# aparture_v1_controller.net
KiCad netlist of a schematic drawn in EAGLE
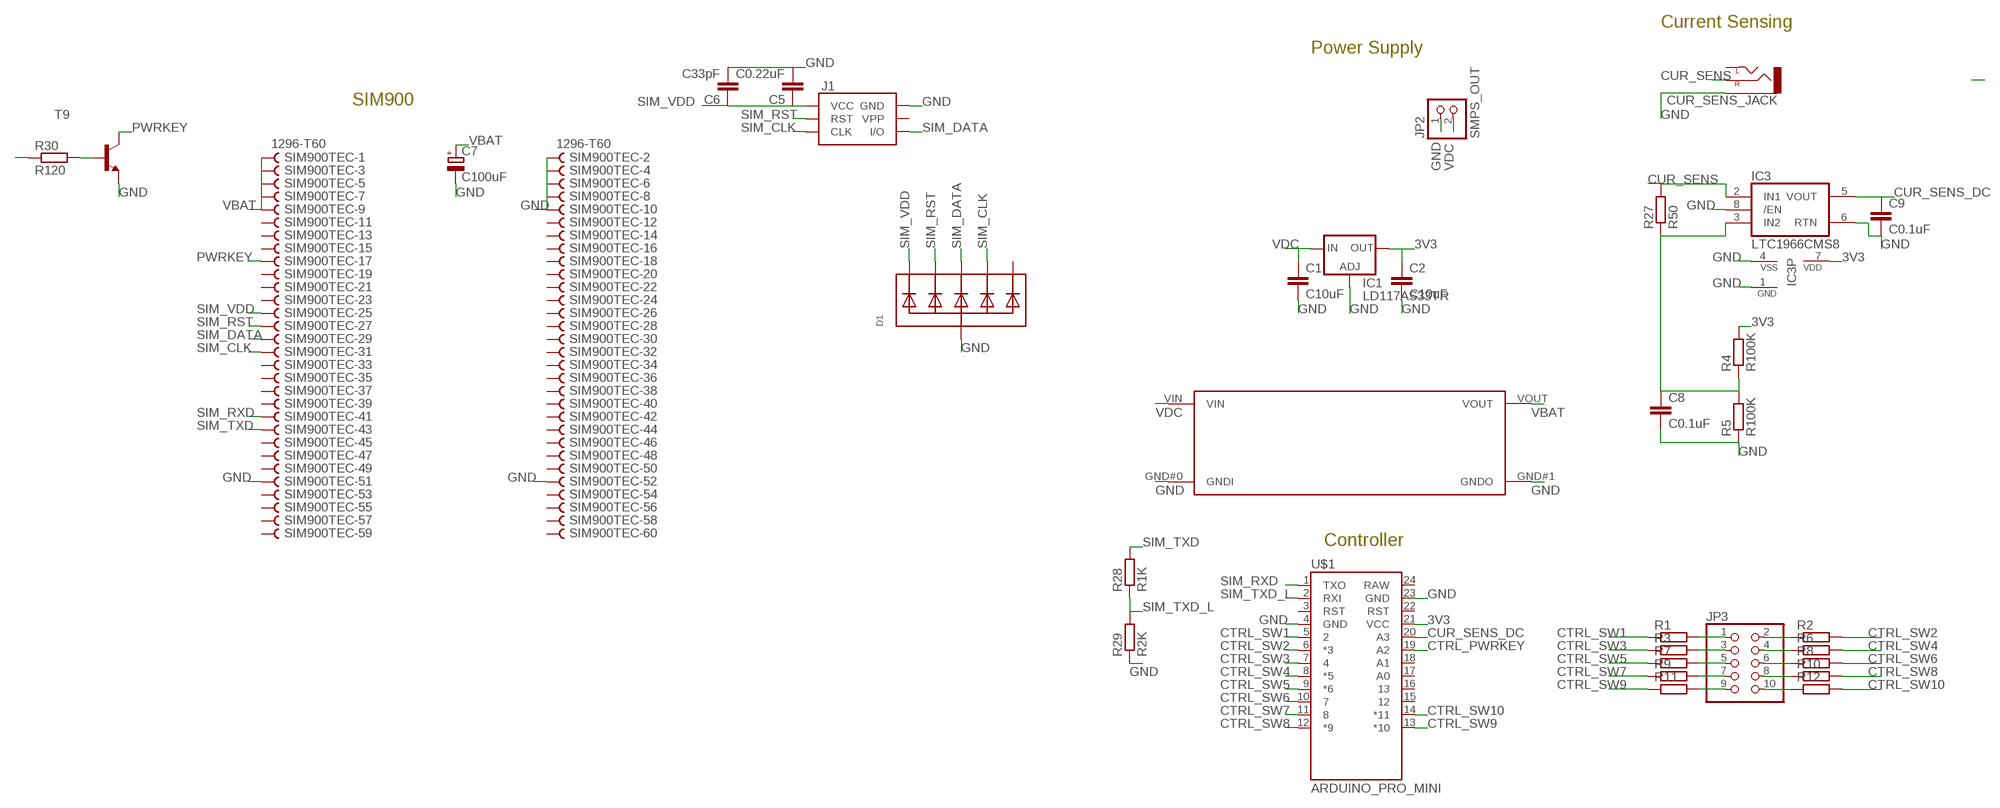
[diagram p0: schematic, sheet 1]

(export (version "E")
  (design (tool "Eeschema 10.0.6"))
  (components
    (comp (ref "C1")
      (value "C10uF")
      (footprint "eagle-import:C0805")
      (libsource (lib "eagle-import") (part "C-EUC0805"))
    )
    (comp (ref "C2")
      (value "C10uF")
      (footprint "eagle-import:C0805")
      (libsource (lib "eagle-import") (part "C-EUC0805"))
    )
    (comp (ref "C5")
      (value "C0.22uF")
      (footprint "eagle-import:C0805")
      (libsource (lib "eagle-import") (part "C-EUC0805"))
    )
    (comp (ref "C6")
      (value "C33pF")
      (footprint "eagle-import:C0805")
      (libsource (lib "eagle-import") (part "C-EUC0805"))
    )
    (comp (ref "C7")
      (value "C100uF")
      (footprint "eagle-import:153CLV-0605")
      (libsource (lib "eagle-import") (part "CPOL-EU153CLV-0605"))
    )
    (comp (ref "C8")
      (value "C0.1uF")
      (footprint "eagle-import:C0805")
      (libsource (lib "eagle-import") (part "C-EUC0805"))
    )
    (comp (ref "C9")
      (value "C0.1uF")
      (footprint "eagle-import:C0805")
      (libsource (lib "eagle-import") (part "C-EUC0805"))
    )
    (comp (ref "CUR_SENS_JACK")
      (value "AUDIO-JACKSMD2")
      (footprint "eagle-import:AUDIO-JACK-3.5MM-SMD")
      (libsource (lib "eagle-import") (part "AUDIO-JACKSMD2"))
    )
    (comp (ref "D1")
      (value "TVSARRAY_5LANE")
      (footprint "eagle-import:SOT363")
      (libsource (lib "eagle-import") (part "TVSARRAY_5LANE"))
    )
    (comp (ref "IC1")
      (value "LD117AS33TR")
      (footprint "eagle-import:SOT223")
      (libsource (lib "eagle-import") (part "LD117A?S33TR"))
    )
    (comp (ref "IC3")
      (value "LTC1966CMS8")
      (footprint "eagle-import:MSOP8")
      (libsource (lib "eagle-import") (part "LTC1966MS8C"))
    )
    (comp (ref "J1")
      (value "SIMHOLDERSIM")
      (footprint "eagle-import:SIMHOLDER")
      (libsource (lib "eagle-import") (part "SIMHOLDERSIM"))
    )
    (comp (ref "JP2")
      (value "SMPS_OUT")
      (footprint "eagle-import:1X02")
      (libsource (lib "eagle-import") (part "PINHD-1X2"))
    )
    (comp (ref "JP3")
      (value "PINHD-2X5")
      (footprint "eagle-import:2X05")
      (libsource (lib "eagle-import") (part "PINHD-2X5"))
    )
    (comp (ref "R1")
      (value "R-EU_R0603")
      (footprint "eagle-import:R0603")
      (libsource (lib "eagle-import") (part "R-EU_R0603"))
    )
    (comp (ref "R2")
      (value "R-EU_R0603")
      (footprint "eagle-import:R0603")
      (libsource (lib "eagle-import") (part "R-EU_R0603"))
    )
    (comp (ref "R3")
      (value "R-EU_R0603")
      (footprint "eagle-import:R0603")
      (libsource (lib "eagle-import") (part "R-EU_R0603"))
    )
    (comp (ref "R4")
      (value "R100K")
      (footprint "eagle-import:M0805")
      (libsource (lib "eagle-import") (part "resistor_R-EU_M0805"))
    )
    (comp (ref "R5")
      (value "R100K")
      (footprint "eagle-import:M0805")
      (libsource (lib "eagle-import") (part "resistor_R-EU_M0805"))
    )
    (comp (ref "R6")
      (value "R-EU_R0603")
      (footprint "eagle-import:R0603")
      (libsource (lib "eagle-import") (part "R-EU_R0603"))
    )
    (comp (ref "R7")
      (value "R-EU_R0603")
      (footprint "eagle-import:R0603")
      (libsource (lib "eagle-import") (part "R-EU_R0603"))
    )
    (comp (ref "R8")
      (value "R-EU_R0603")
      (footprint "eagle-import:R0603")
      (libsource (lib "eagle-import") (part "R-EU_R0603"))
    )
    (comp (ref "R9")
      (value "R-EU_R0603")
      (footprint "eagle-import:R0603")
      (libsource (lib "eagle-import") (part "R-EU_R0603"))
    )
    (comp (ref "R10")
      (value "R-EU_R0603")
      (footprint "eagle-import:R0603")
      (libsource (lib "eagle-import") (part "R-EU_R0603"))
    )
    (comp (ref "R11")
      (value "R-EU_R0603")
      (footprint "eagle-import:R0603")
      (libsource (lib "eagle-import") (part "R-EU_R0603"))
    )
    (comp (ref "R12")
      (value "R-EU_R0603")
      (footprint "eagle-import:R0603")
      (libsource (lib "eagle-import") (part "R-EU_R0603"))
    )
    (comp (ref "R27")
      (value "R50")
      (footprint "eagle-import:M0805")
      (libsource (lib "eagle-import") (part "resistor_R-EU_M0805"))
    )
    (comp (ref "R28")
      (value "R1K")
      (footprint "eagle-import:M0805")
      (libsource (lib "eagle-import") (part "resistor_R-EU_M0805"))
    )
    (comp (ref "R29")
      (value "R2K")
      (footprint "eagle-import:M0805")
      (libsource (lib "eagle-import") (part "resistor_R-EU_M0805"))
    )
    (comp (ref "R30")
      (value "R120")
      (footprint "eagle-import:M0805")
      (libsource (lib "eagle-import") (part "resistor_R-EU_M0805"))
    )
    (comp (ref "SIM900TEC")
      (value "1296-T60")
      (footprint "eagle-import:1296-60")
      (libsource (lib "eagle-import") (part "1296-T60"))
    )
    (comp (ref "T9")
      (value "MMBT2222ALT1-NPN-SOT23-BEC")
      (footprint "eagle-import:SOT23-BEC")
      (libsource (lib "eagle-import") (part "-NPN-SOT23-BECMMBT2222ALT1"))
    )
    (comp (ref "U$1")
      (value "ARDUINO_PRO_MINI")
      (footprint "eagle-import:ARDUINO_PRO_MINI")
      (libsource (lib "eagle-import") (part "ARDUINO_PRO_MINI"))
    )
    (comp (ref "VOL_REG_SIM900")
      (value "DCDCMODULE")
      (footprint "eagle-import:DCDCMODULE")
      (libsource (lib "eagle-import") (part "DCDCMODULE"))
    )
  )
  (nets
    (net (code "1") (name "/3V3") (class "Default")
      (node (ref "C2") (pin "1") (pinfunction "1_1") (pintype "passive"))
      (node (ref "IC1") (pin "4") (pinfunction "OUT_4") (pintype "passive"))
      (node (ref "IC3") (pin "7") (pinfunction "VDD_7") (pintype "power_in"))
      (node (ref "R4") (pin "2") (pinfunction "2_2") (pintype "passive"))
      (node (ref "U$1") (pin "21") (pinfunction "VCC_21") (pintype "bidirectional"))
    )
    (net (code "2") (name "/CTRL_PWRKEY") (class "Default")
      (node (ref "R30") (pin "1") (pinfunction "1_1") (pintype "passive"))
      (node (ref "U$1") (pin "19") (pinfunction "A2_19") (pintype "bidirectional"))
    )
    (net (code "3") (name "/CTRL_SW1") (class "Default")
      (node (ref "R1") (pin "1") (pinfunction "1_1") (pintype "passive"))
      (node (ref "U$1") (pin "5") (pinfunction "2_5") (pintype "bidirectional"))
    )
    (net (code "4") (name "/CTRL_SW2") (class "Default")
      (node (ref "R2") (pin "2") (pinfunction "2_2") (pintype "passive"))
      (node (ref "U$1") (pin "6") (pinfunction "*3_6") (pintype "bidirectional"))
    )
    (net (code "5") (name "/CTRL_SW3") (class "Default")
      (node (ref "R3") (pin "1") (pinfunction "1_1") (pintype "passive"))
      (node (ref "U$1") (pin "7") (pinfunction "4_7") (pintype "bidirectional"))
    )
    (net (code "6") (name "/CTRL_SW4") (class "Default")
      (node (ref "R6") (pin "2") (pinfunction "2_2") (pintype "passive"))
      (node (ref "U$1") (pin "8") (pinfunction "*5_8") (pintype "bidirectional"))
    )
    (net (code "7") (name "/CTRL_SW5") (class "Default")
      (node (ref "R7") (pin "1") (pinfunction "1_1") (pintype "passive"))
      (node (ref "U$1") (pin "9") (pinfunction "*6_9") (pintype "bidirectional"))
    )
    (net (code "8") (name "/CTRL_SW6") (class "Default")
      (node (ref "R8") (pin "2") (pinfunction "2_2") (pintype "passive"))
      (node (ref "U$1") (pin "10") (pinfunction "7_10") (pintype "bidirectional"))
    )
    (net (code "9") (name "/CTRL_SW7") (class "Default")
      (node (ref "R9") (pin "1") (pinfunction "1_1") (pintype "passive"))
      (node (ref "U$1") (pin "11") (pinfunction "8_11") (pintype "bidirectional"))
    )
    (net (code "10") (name "/CTRL_SW8") (class "Default")
      (node (ref "R10") (pin "2") (pinfunction "2_2") (pintype "passive"))
      (node (ref "U$1") (pin "12") (pinfunction "*9_12") (pintype "bidirectional"))
    )
    (net (code "11") (name "/CTRL_SW9") (class "Default")
      (node (ref "R11") (pin "1") (pinfunction "1_1") (pintype "passive"))
      (node (ref "U$1") (pin "13") (pinfunction "*10_13") (pintype "bidirectional"))
    )
    (net (code "12") (name "/CTRL_SW10") (class "Default")
      (node (ref "R12") (pin "2") (pinfunction "2_2") (pintype "passive"))
      (node (ref "U$1") (pin "14") (pinfunction "*11_14") (pintype "bidirectional"))
    )
    (net (code "13") (name "/CUR_SENS") (class "Default")
      (node (ref "CUR_SENS_JACK") (pin "RING") (pinfunction "RIGHT_RING") (pintype "bidirectional"))
      (node (ref "IC3") (pin "2") (pinfunction "IN1_2") (pintype "input"))
      (node (ref "R27") (pin "2") (pinfunction "2_2") (pintype "passive"))
    )
    (net (code "14") (name "/CUR_SENS_DC") (class "Default")
      (node (ref "C9") (pin "1") (pinfunction "1_1") (pintype "passive"))
      (node (ref "IC3") (pin "5") (pinfunction "VOUT_5") (pintype "output"))
      (node (ref "U$1") (pin "20") (pinfunction "A3_20") (pintype "bidirectional"))
    )
    (net (code "15") (name "/GND") (class "Default")
      (node (ref "C1") (pin "2") (pinfunction "2_2") (pintype "passive"))
      (node (ref "C2") (pin "2") (pinfunction "2_2") (pintype "passive"))
      (node (ref "C5") (pin "2") (pinfunction "2_2") (pintype "passive"))
      (node (ref "C6") (pin "2") (pinfunction "2_2") (pintype "passive"))
      (node (ref "C7") (pin "-") (pinfunction "-_-") (pintype "passive"))
      (node (ref "C8") (pin "2") (pinfunction "2_2") (pintype "passive"))
      (node (ref "C9") (pin "2") (pinfunction "2_2") (pintype "passive"))
      (node (ref "CUR_SENS_JACK") (pin "SLEEVE") (pinfunction "SLEEVE_SLEEVE") (pintype "bidirectional"))
      (node (ref "D1") (pin "2") (pinfunction "A_2") (pintype "passive"))
      (node (ref "IC1") (pin "1") (pinfunction "ADJ_1") (pintype "input"))
      (node (ref "IC3") (pin "1") (pinfunction "GND_1") (pintype "power_in"))
      (node (ref "IC3") (pin "4") (pinfunction "VSS_4") (pintype "power_in"))
      (node (ref "IC3") (pin "6") (pinfunction "RTN_6") (pintype "passive"))
      (node (ref "IC3") (pin "8") (pinfunction "/EN_8") (pintype "input"))
      (node (ref "J1") (pin "C5") (pinfunction "GND_C5") (pintype "power_in"))
      (node (ref "JP2") (pin "1") (pinfunction "1_1") (pintype "passive"))
      (node (ref "R29") (pin "1") (pinfunction "1_1") (pintype "passive"))
      (node (ref "R5") (pin "1") (pinfunction "1_1") (pintype "passive"))
      (node (ref "SIM900TEC") (pin "10") (pinfunction "B_10") (pintype "passive"))
      (node (ref "SIM900TEC") (pin "2") (pinfunction "B_2") (pintype "passive"))
      (node (ref "SIM900TEC") (pin "4") (pinfunction "B_4") (pintype "passive"))
      (node (ref "SIM900TEC") (pin "51") (pinfunction "B_51") (pintype "passive"))
      (node (ref "SIM900TEC") (pin "52") (pinfunction "B_52") (pintype "passive"))
      (node (ref "SIM900TEC") (pin "6") (pinfunction "B_6") (pintype "passive"))
      (node (ref "SIM900TEC") (pin "8") (pinfunction "B_8") (pintype "passive"))
      (node (ref "T9") (pin "E") (pinfunction "E_E") (pintype "passive"))
      (node (ref "U$1") (pin "23") (pinfunction "GND_23") (pintype "bidirectional"))
      (node (ref "U$1") (pin "4") (pinfunction "GND_4") (pintype "bidirectional"))
      (node (ref "VOL_REG_SIM900") (pin "GND#0") (pinfunction "GNDI_GND#0") (pintype "bidirectional"))
      (node (ref "VOL_REG_SIM900") (pin "GND#1") (pinfunction "GNDO_GND#1") (pintype "bidirectional"))
    )
    (net (code "16") (name "/PWRKEY") (class "Default")
      (node (ref "SIM900TEC") (pin "17") (pinfunction "B_17") (pintype "passive"))
      (node (ref "T9") (pin "C") (pinfunction "C_C") (pintype "passive"))
    )
    (net (code "17") (name "/SIM_CLK") (class "Default")
      (node (ref "D1") (pin "5") (pinfunction "C4_5") (pintype "passive"))
      (node (ref "J1") (pin "C3") (pinfunction "CLK_C3") (pintype "input"))
      (node (ref "SIM900TEC") (pin "31") (pinfunction "B_31") (pintype "passive"))
    )
    (net (code "18") (name "/SIM_DATA") (class "Default")
      (node (ref "D1") (pin "4") (pinfunction "C3_4") (pintype "passive"))
      (node (ref "J1") (pin "C7") (pinfunction "I/O_C7") (pintype "bidirectional"))
      (node (ref "SIM900TEC") (pin "29") (pinfunction "B_29") (pintype "passive"))
    )
    (net (code "19") (name "/SIM_RST") (class "Default")
      (node (ref "D1") (pin "3") (pinfunction "C2_3") (pintype "passive"))
      (node (ref "J1") (pin "C2") (pinfunction "RST_C2") (pintype "input"))
      (node (ref "SIM900TEC") (pin "27") (pinfunction "B_27") (pintype "passive"))
    )
    (net (code "20") (name "/SIM_RXD") (class "Default")
      (node (ref "SIM900TEC") (pin "41") (pinfunction "B_41") (pintype "passive"))
      (node (ref "U$1") (pin "1") (pinfunction "TXO_1") (pintype "bidirectional"))
    )
    (net (code "21") (name "/SIM_TXD") (class "Default")
      (node (ref "R28") (pin "2") (pinfunction "2_2") (pintype "passive"))
      (node (ref "SIM900TEC") (pin "43") (pinfunction "B_43") (pintype "passive"))
    )
    (net (code "22") (name "/SIM_TXD_L") (class "Default")
      (node (ref "R28") (pin "1") (pinfunction "1_1") (pintype "passive"))
      (node (ref "R29") (pin "2") (pinfunction "2_2") (pintype "passive"))
      (node (ref "U$1") (pin "2") (pinfunction "RXI_2") (pintype "bidirectional"))
    )
    (net (code "23") (name "/SIM_VDD") (class "Default")
      (node (ref "C5") (pin "1") (pinfunction "1_1") (pintype "passive"))
      (node (ref "C6") (pin "1") (pinfunction "1_1") (pintype "passive"))
      (node (ref "D1") (pin "1") (pinfunction "C1_1") (pintype "passive"))
      (node (ref "J1") (pin "C1") (pinfunction "VCC_C1") (pintype "power_in"))
      (node (ref "SIM900TEC") (pin "25") (pinfunction "B_25") (pintype "passive"))
    )
    (net (code "24") (name "/VBAT") (class "Default")
      (node (ref "C7") (pin "+") (pinfunction "+_+") (pintype "passive"))
      (node (ref "SIM900TEC") (pin "1") (pinfunction "B_1") (pintype "passive"))
      (node (ref "SIM900TEC") (pin "3") (pinfunction "B_3") (pintype "passive"))
      (node (ref "SIM900TEC") (pin "5") (pinfunction "B_5") (pintype "passive"))
      (node (ref "SIM900TEC") (pin "7") (pinfunction "B_7") (pintype "passive"))
      (node (ref "SIM900TEC") (pin "9") (pinfunction "B_9") (pintype "passive"))
      (node (ref "VOL_REG_SIM900") (pin "VOUT") (pinfunction "VOUT_VOUT") (pintype "bidirectional"))
    )
    (net (code "25") (name "/VDC") (class "Default")
      (node (ref "C1") (pin "1") (pinfunction "1_1") (pintype "passive"))
      (node (ref "IC1") (pin "3") (pinfunction "IN_3") (pintype "input"))
      (node (ref "JP2") (pin "2") (pinfunction "2_2") (pintype "passive"))
      (node (ref "VOL_REG_SIM900") (pin "VIN") (pinfunction "VIN_VIN") (pintype "bidirectional"))
    )
    (net (code "26") (name "Net-(IC3A-IN2)") (class "Default")
      (node (ref "C8") (pin "1") (pinfunction "1_1") (pintype "passive"))
      (node (ref "IC3") (pin "3") (pinfunction "IN2_3") (pintype "input"))
      (node (ref "R27") (pin "1") (pinfunction "1_1") (pintype "passive"))
      (node (ref "R4") (pin "1") (pinfunction "1_1") (pintype "passive"))
      (node (ref "R5") (pin "2") (pinfunction "2_2") (pintype "passive"))
    )
    (net (code "27") (name "Net-(JP3-Pad1)") (class "Default")
      (node (ref "JP3") (pin "1") (pinfunction "1_1") (pintype "passive"))
      (node (ref "R1") (pin "2") (pinfunction "2_2") (pintype "passive"))
    )
    (net (code "28") (name "Net-(JP3-Pad2)") (class "Default")
      (node (ref "JP3") (pin "2") (pinfunction "2_2") (pintype "passive"))
      (node (ref "R2") (pin "1") (pinfunction "1_1") (pintype "passive"))
    )
    (net (code "29") (name "Net-(JP3-Pad3)") (class "Default")
      (node (ref "JP3") (pin "3") (pinfunction "3_3") (pintype "passive"))
      (node (ref "R3") (pin "2") (pinfunction "2_2") (pintype "passive"))
    )
    (net (code "30") (name "Net-(JP3-Pad4)") (class "Default")
      (node (ref "JP3") (pin "4") (pinfunction "4_4") (pintype "passive"))
      (node (ref "R6") (pin "1") (pinfunction "1_1") (pintype "passive"))
    )
    (net (code "31") (name "Net-(JP3-Pad5)") (class "Default")
      (node (ref "JP3") (pin "5") (pinfunction "5_5") (pintype "passive"))
      (node (ref "R7") (pin "2") (pinfunction "2_2") (pintype "passive"))
    )
    (net (code "32") (name "Net-(JP3-Pad6)") (class "Default")
      (node (ref "JP3") (pin "6") (pinfunction "6_6") (pintype "passive"))
      (node (ref "R8") (pin "1") (pinfunction "1_1") (pintype "passive"))
    )
    (net (code "33") (name "Net-(JP3-Pad7)") (class "Default")
      (node (ref "JP3") (pin "7") (pinfunction "7_7") (pintype "passive"))
      (node (ref "R9") (pin "2") (pinfunction "2_2") (pintype "passive"))
    )
    (net (code "34") (name "Net-(JP3-Pad8)") (class "Default")
      (node (ref "JP3") (pin "8") (pinfunction "8_8") (pintype "passive"))
      (node (ref "R10") (pin "1") (pinfunction "1_1") (pintype "passive"))
    )
    (net (code "35") (name "Net-(JP3-Pad9)") (class "Default")
      (node (ref "JP3") (pin "9") (pinfunction "9_9") (pintype "passive"))
      (node (ref "R11") (pin "2") (pinfunction "2_2") (pintype "passive"))
    )
    (net (code "36") (name "Net-(JP3-Pad10)") (class "Default")
      (node (ref "JP3") (pin "10") (pinfunction "10_10") (pintype "passive"))
      (node (ref "R12") (pin "1") (pinfunction "1_1") (pintype "passive"))
    )
    (net (code "37") (name "Net-(R30-Pad2)") (class "Default")
      (node (ref "R30") (pin "2") (pinfunction "2_2") (pintype "passive"))
      (node (ref "T9") (pin "B") (pinfunction "B_B") (pintype "passive"))
    )
    (net (code "38") (name "unconnected-(CUR_SENS_JACK-LEFT-PadTIP)") (class "Default")
      (node (ref "CUR_SENS_JACK") (pin "TIP") (pinfunction "LEFT_TIP") (pintype "bidirectional"))
    )
    (net (code "39") (name "unconnected-(D1-C5-Pad6)") (class "Default")
      (node (ref "D1") (pin "6") (pinfunction "C5_6") (pintype "passive"))
    )
    (net (code "40") (name "unconnected-(J1-VPP-PadC6)") (class "Default")
      (node (ref "J1") (pin "C6") (pinfunction "VPP_C6") (pintype "input"))
    )
    (net (code "41") (name "unconnected-(SIM900TECAA-B-Pad33)") (class "Default")
      (node (ref "SIM900TEC") (pin "33") (pinfunction "B_33") (pintype "passive"))
    )
    (net (code "42") (name "unconnected-(SIM900TECAB-B-Pad34)") (class "Default")
      (node (ref "SIM900TEC") (pin "34") (pinfunction "B_34") (pintype "passive"))
    )
    (net (code "43") (name "unconnected-(SIM900TECAC-B-Pad35)") (class "Default")
      (node (ref "SIM900TEC") (pin "35") (pinfunction "B_35") (pintype "passive"))
    )
    (net (code "44") (name "unconnected-(SIM900TECAD-B-Pad36)") (class "Default")
      (node (ref "SIM900TEC") (pin "36") (pinfunction "B_36") (pintype "passive"))
    )
    (net (code "45") (name "unconnected-(SIM900TECAE-B-Pad37)") (class "Default")
      (node (ref "SIM900TEC") (pin "37") (pinfunction "B_37") (pintype "passive"))
    )
    (net (code "46") (name "unconnected-(SIM900TECAF-B-Pad38)") (class "Default")
      (node (ref "SIM900TEC") (pin "38") (pinfunction "B_38") (pintype "passive"))
    )
    (net (code "47") (name "unconnected-(SIM900TECAG-B-Pad39)") (class "Default")
      (node (ref "SIM900TEC") (pin "39") (pinfunction "B_39") (pintype "passive"))
    )
    (net (code "48") (name "unconnected-(SIM900TECAI-B-Pad40)") (class "Default")
      (node (ref "SIM900TEC") (pin "40") (pinfunction "B_40") (pintype "passive"))
    )
    (net (code "49") (name "unconnected-(SIM900TECAK-B-Pad42)") (class "Default")
      (node (ref "SIM900TEC") (pin "42") (pinfunction "B_42") (pintype "passive"))
    )
    (net (code "50") (name "unconnected-(SIM900TECAM-B-Pad44)") (class "Default")
      (node (ref "SIM900TEC") (pin "44") (pinfunction "B_44") (pintype "passive"))
    )
    (net (code "51") (name "unconnected-(SIM900TECAN-B-Pad45)") (class "Default")
      (node (ref "SIM900TEC") (pin "45") (pinfunction "B_45") (pintype "passive"))
    )
    (net (code "52") (name "unconnected-(SIM900TECAO-B-Pad46)") (class "Default")
      (node (ref "SIM900TEC") (pin "46") (pinfunction "B_46") (pintype "passive"))
    )
    (net (code "53") (name "unconnected-(SIM900TECAP-B-Pad47)") (class "Default")
      (node (ref "SIM900TEC") (pin "47") (pinfunction "B_47") (pintype "passive"))
    )
    (net (code "54") (name "unconnected-(SIM900TECAQ-B-Pad48)") (class "Default")
      (node (ref "SIM900TEC") (pin "48") (pinfunction "B_48") (pintype "passive"))
    )
    (net (code "55") (name "unconnected-(SIM900TECAR-B-Pad49)") (class "Default")
      (node (ref "SIM900TEC") (pin "49") (pinfunction "B_49") (pintype "passive"))
    )
    (net (code "56") (name "unconnected-(SIM900TECAT-B-Pad50)") (class "Default")
      (node (ref "SIM900TEC") (pin "50") (pinfunction "B_50") (pintype "passive"))
    )
    (net (code "57") (name "unconnected-(SIM900TECAW-B-Pad53)") (class "Default")
      (node (ref "SIM900TEC") (pin "53") (pinfunction "B_53") (pintype "passive"))
    )
    (net (code "58") (name "unconnected-(SIM900TECAX-B-Pad54)") (class "Default")
      (node (ref "SIM900TEC") (pin "54") (pinfunction "B_54") (pintype "passive"))
    )
    (net (code "59") (name "unconnected-(SIM900TECAY-B-Pad55)") (class "Default")
      (node (ref "SIM900TEC") (pin "55") (pinfunction "B_55") (pintype "passive"))
    )
    (net (code "60") (name "unconnected-(SIM900TECAZ-B-Pad56)") (class "Default")
      (node (ref "SIM900TEC") (pin "56") (pinfunction "B_56") (pintype "passive"))
    )
    (net (code "61") (name "unconnected-(SIM900TECBA-B-Pad57)") (class "Default")
      (node (ref "SIM900TEC") (pin "57") (pinfunction "B_57") (pintype "passive"))
    )
    (net (code "62") (name "unconnected-(SIM900TECBB-B-Pad58)") (class "Default")
      (node (ref "SIM900TEC") (pin "58") (pinfunction "B_58") (pintype "passive"))
    )
    (net (code "63") (name "unconnected-(SIM900TECBC-B-Pad59)") (class "Default")
      (node (ref "SIM900TEC") (pin "59") (pinfunction "B_59") (pintype "passive"))
    )
    (net (code "64") (name "unconnected-(SIM900TECBE-B-Pad60)") (class "Default")
      (node (ref "SIM900TEC") (pin "60") (pinfunction "B_60") (pintype "passive"))
    )
    (net (code "65") (name "unconnected-(SIM900TECC-B-Pad11)") (class "Default")
      (node (ref "SIM900TEC") (pin "11") (pinfunction "B_11") (pintype "passive"))
    )
    (net (code "66") (name "unconnected-(SIM900TECD-B-Pad12)") (class "Default")
      (node (ref "SIM900TEC") (pin "12") (pinfunction "B_12") (pintype "passive"))
    )
    (net (code "67") (name "unconnected-(SIM900TECE-B-Pad13)") (class "Default")
      (node (ref "SIM900TEC") (pin "13") (pinfunction "B_13") (pintype "passive"))
    )
    (net (code "68") (name "unconnected-(SIM900TECF-B-Pad14)") (class "Default")
      (node (ref "SIM900TEC") (pin "14") (pinfunction "B_14") (pintype "passive"))
    )
    (net (code "69") (name "unconnected-(SIM900TECG-B-Pad15)") (class "Default")
      (node (ref "SIM900TEC") (pin "15") (pinfunction "B_15") (pintype "passive"))
    )
    (net (code "70") (name "unconnected-(SIM900TECH-B-Pad16)") (class "Default")
      (node (ref "SIM900TEC") (pin "16") (pinfunction "B_16") (pintype "passive"))
    )
    (net (code "71") (name "unconnected-(SIM900TECJ-B-Pad18)") (class "Default")
      (node (ref "SIM900TEC") (pin "18") (pinfunction "B_18") (pintype "passive"))
    )
    (net (code "72") (name "unconnected-(SIM900TECK-B-Pad19)") (class "Default")
      (node (ref "SIM900TEC") (pin "19") (pinfunction "B_19") (pintype "passive"))
    )
    (net (code "73") (name "unconnected-(SIM900TECM-B-Pad20)") (class "Default")
      (node (ref "SIM900TEC") (pin "20") (pinfunction "B_20") (pintype "passive"))
    )
    (net (code "74") (name "unconnected-(SIM900TECN-B-Pad21)") (class "Default")
      (node (ref "SIM900TEC") (pin "21") (pinfunction "B_21") (pintype "passive"))
    )
    (net (code "75") (name "unconnected-(SIM900TECO-B-Pad22)") (class "Default")
      (node (ref "SIM900TEC") (pin "22") (pinfunction "B_22") (pintype "passive"))
    )
    (net (code "76") (name "unconnected-(SIM900TECP-B-Pad23)") (class "Default")
      (node (ref "SIM900TEC") (pin "23") (pinfunction "B_23") (pintype "passive"))
    )
    (net (code "77") (name "unconnected-(SIM900TECQ-B-Pad24)") (class "Default")
      (node (ref "SIM900TEC") (pin "24") (pinfunction "B_24") (pintype "passive"))
    )
    (net (code "78") (name "unconnected-(SIM900TECS-B-Pad26)") (class "Default")
      (node (ref "SIM900TEC") (pin "26") (pinfunction "B_26") (pintype "passive"))
    )
    (net (code "79") (name "unconnected-(SIM900TECU-B-Pad28)") (class "Default")
      (node (ref "SIM900TEC") (pin "28") (pinfunction "B_28") (pintype "passive"))
    )
    (net (code "80") (name "unconnected-(SIM900TECX-B-Pad30)") (class "Default")
      (node (ref "SIM900TEC") (pin "30") (pinfunction "B_30") (pintype "passive"))
    )
    (net (code "81") (name "unconnected-(SIM900TECZ-B-Pad32)") (class "Default")
      (node (ref "SIM900TEC") (pin "32") (pinfunction "B_32") (pintype "passive"))
    )
    (net (code "82") (name "unconnected-(U$1-12-Pad15)") (class "Default")
      (node (ref "U$1") (pin "15") (pinfunction "12_15") (pintype "bidirectional"))
    )
    (net (code "83") (name "unconnected-(U$1-13-Pad16)") (class "Default")
      (node (ref "U$1") (pin "16") (pinfunction "13_16") (pintype "bidirectional"))
    )
    (net (code "84") (name "unconnected-(U$1-A0-Pad17)") (class "Default")
      (node (ref "U$1") (pin "17") (pinfunction "A0_17") (pintype "bidirectional"))
    )
    (net (code "85") (name "unconnected-(U$1-A1-Pad18)") (class "Default")
      (node (ref "U$1") (pin "18") (pinfunction "A1_18") (pintype "bidirectional"))
    )
    (net (code "86") (name "unconnected-(U$1-RAW-Pad24)") (class "Default")
      (node (ref "U$1") (pin "24") (pinfunction "RAW_24") (pintype "bidirectional"))
    )
    (net (code "87") (name "unconnected-(U$1-RST-Pad3)") (class "Default")
      (node (ref "U$1") (pin "3") (pinfunction "RST_3") (pintype "bidirectional"))
    )
    (net (code "88") (name "unconnected-(U$1-RST-Pad22)") (class "Default")
      (node (ref "U$1") (pin "22") (pinfunction "RST_22") (pintype "bidirectional"))
    )
  )
)
